# 9_-_STM32F407_Controller.net
KiCad netlist of a schematic drawn in Altium Designer
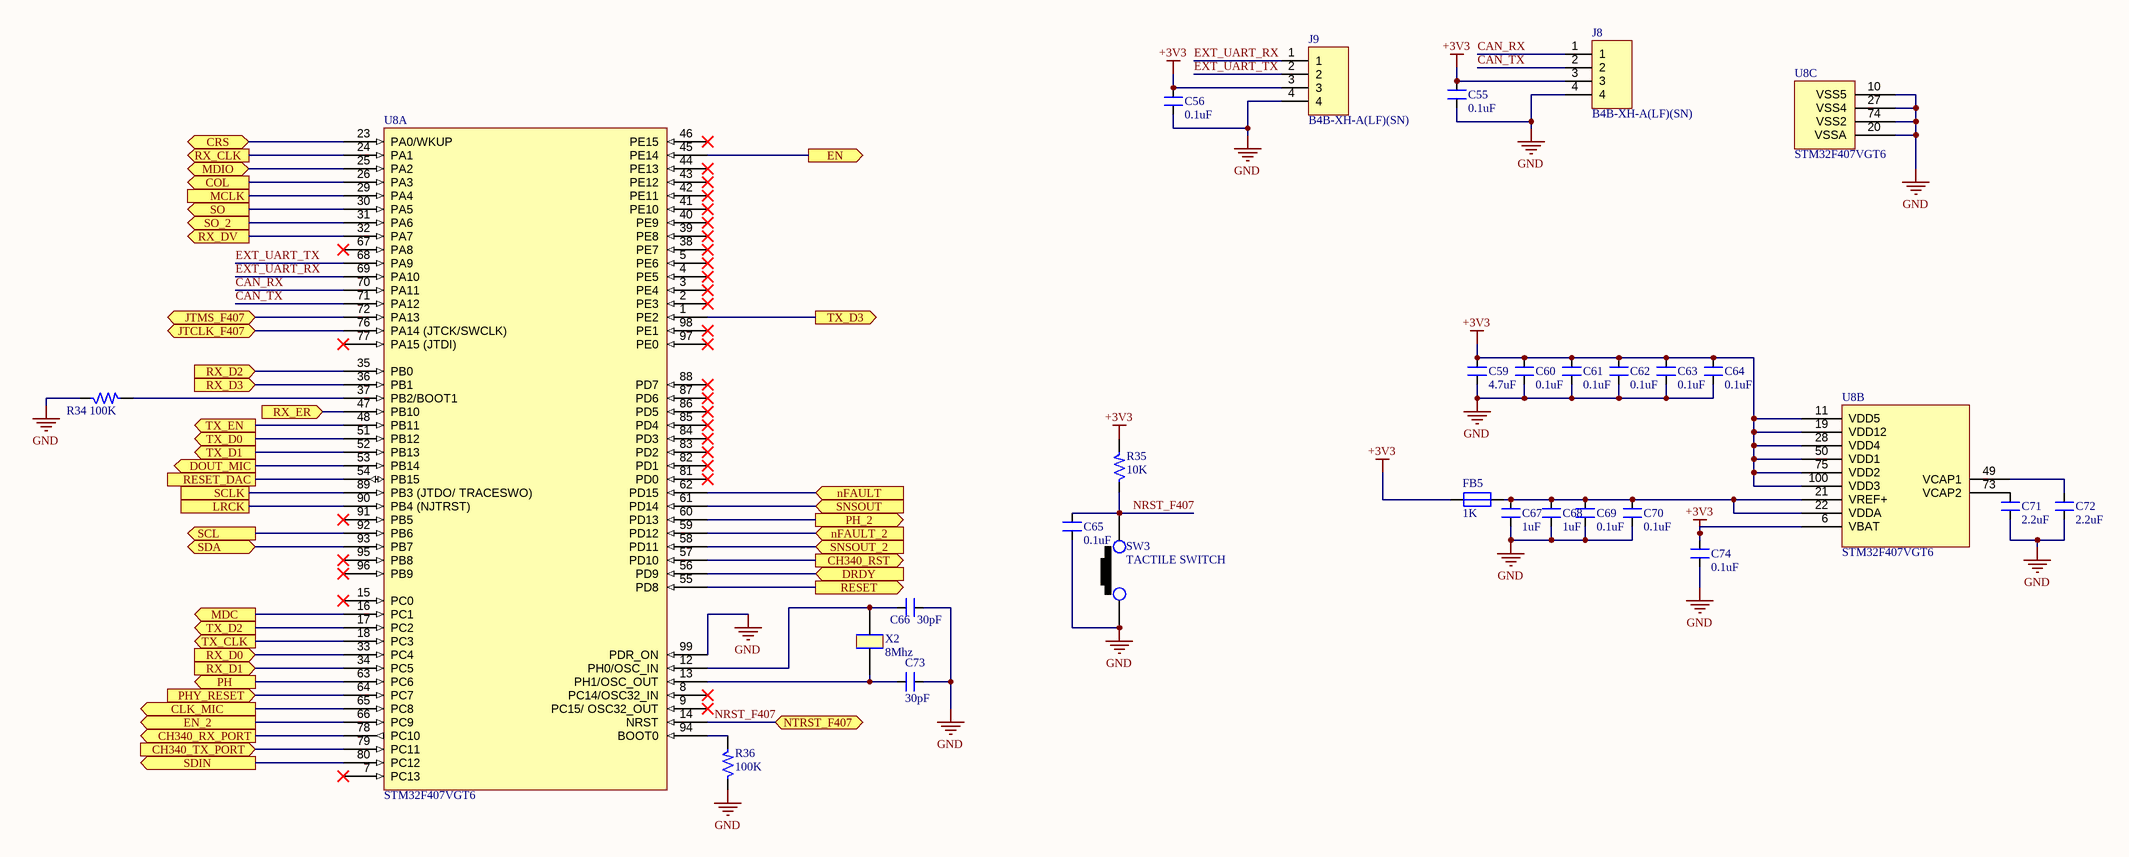
[diagram p0: [9] - STM32F407 Controller.SchDoc]

(export (version "E")
  (design (tool "Eeschema 10.0.6"))
  (components
    (comp (ref "C55")
      (value "0.1uF")
      (footprint "CAP_0805")
      (description "0.1µF ±10% 50V Ceramic Capacitor X7R 0805 (2012 Metric)")
      (fields
        (field (name "MANUFACTURER") "Samsung")
        (field (name "MANUFACTURER PART NUMBER") "CL21B104KBCNNNC")
      )
      (libsource (lib "ESTEEMPCBLIB") (part "CAP_0.1uF-50V-10%-0805"))
    )
    (comp (ref "C56")
      (value "0.1uF")
      (footprint "CAP_0805")
      (description "0.1µF ±10% 50V Ceramic Capacitor X7R 0805 (2012 Metric)")
      (fields
        (field (name "MANUFACTURER") "Samsung")
        (field (name "MANUFACTURER PART NUMBER") "CL21B104KBCNNNC")
      )
      (libsource (lib "ESTEEMPCBLIB") (part "CAP_0.1uF-50V-10%-0805"))
    )
    (comp (ref "C59")
      (value "4.7uF")
      (footprint "CAP_0805")
      (description "0.1µF ±10% 50V Ceramic Capacitor X7R 0805 (2012 Metric)")
      (fields
        (field (name "MANUFACTURER") "Samsung")
        (field (name "MANUFACTURER PART NUMBER") "CL21B104KBCNNNC")
      )
      (libsource (lib "ESTEEMPCBLIB") (part "CAP_0.1uF-50V-10%-0805"))
    )
    (comp (ref "C60")
      (value "0.1uF")
      (footprint "CAP_0805")
      (description "0.1µF ±10% 50V Ceramic Capacitor X7R 0805 (2012 Metric)")
      (fields
        (field (name "MANUFACTURER") "Samsung")
        (field (name "MANUFACTURER PART NUMBER") "CL21B104KBCNNNC")
      )
      (libsource (lib "ESTEEMPCBLIB") (part "CAP_0.1uF-50V-10%-0805"))
    )
    (comp (ref "C61")
      (value "0.1uF")
      (footprint "CAP_0805")
      (description "0.1µF ±10% 50V Ceramic Capacitor X7R 0805 (2012 Metric)")
      (fields
        (field (name "MANUFACTURER") "Samsung")
        (field (name "MANUFACTURER PART NUMBER") "CL21B104KBCNNNC")
      )
      (libsource (lib "ESTEEMPCBLIB") (part "CAP_0.1uF-50V-10%-0805"))
    )
    (comp (ref "C62")
      (value "0.1uF")
      (footprint "CAP_0805")
      (description "0.1µF ±10% 50V Ceramic Capacitor X7R 0805 (2012 Metric)")
      (fields
        (field (name "MANUFACTURER") "Samsung")
        (field (name "MANUFACTURER PART NUMBER") "CL21B104KBCNNNC")
      )
      (libsource (lib "ESTEEMPCBLIB") (part "CAP_0.1uF-50V-10%-0805"))
    )
    (comp (ref "C63")
      (value "0.1uF")
      (footprint "CAP_0805")
      (description "0.1µF ±10% 50V Ceramic Capacitor X7R 0805 (2012 Metric)")
      (fields
        (field (name "MANUFACTURER") "Samsung")
        (field (name "MANUFACTURER PART NUMBER") "CL21B104KBCNNNC")
      )
      (libsource (lib "ESTEEMPCBLIB") (part "CAP_0.1uF-50V-10%-0805"))
    )
    (comp (ref "C64")
      (value "0.1uF")
      (footprint "CAP_0805")
      (description "0.1µF ±10% 50V Ceramic Capacitor X7R 0805 (2012 Metric)")
      (fields
        (field (name "MANUFACTURER") "Samsung")
        (field (name "MANUFACTURER PART NUMBER") "CL21B104KBCNNNC")
      )
      (libsource (lib "ESTEEMPCBLIB") (part "CAP_0.1uF-50V-10%-0805"))
    )
    (comp (ref "C65")
      (value "0.1uF")
      (footprint "CAP_0805")
      (description "0.1µF ±10% 50V Ceramic Capacitor X7R 0805 (2012 Metric)")
      (fields
        (field (name "MANUFACTURER") "Samsung")
        (field (name "MANUFACTURER PART NUMBER") "CL21B104KBCNNNC")
      )
      (libsource (lib "ESTEEMPCBLIB") (part "CAP_0.1uF-50V-10%-0805"))
    )
    (comp (ref "C66")
      (value "30pF")
      (footprint "CAP_0805")
      (description "±10% 50V Ceramic Capacitor C0G, NP0 0805 (2012 Metric)")
      (fields
        (field (name "MANUFACTURER PART NUMBER") "C0805C300K5GAC7800")
        (field (name "MANUFACTURER") "KEMET")
      )
      (libsource (lib "ESTEEMPCBLIB") (part "CAP_30pF-50V-10%-0805"))
    )
    (comp (ref "C67")
      (value "1uF")
      (footprint "CAP_0805")
      (description "1µF ±5% 50V Ceramic Capacitor X7R 0805 (2012 Metric)")
      (fields
        (field (name "MANUFACTURER") "Samsung")
        (field (name "MANUFACTURER PART NUMBER") "CC0805JKX7R9BB105")
      )
      (libsource (lib "ESTEEMPCBLIB") (part "CAP_1uF-50V-5%-0805"))
    )
    (comp (ref "C68")
      (value "1uF")
      (footprint "CAP_0805")
      (description "1µF ±5% 50V Ceramic Capacitor X7R 0805 (2012 Metric)")
      (fields
        (field (name "MANUFACTURER") "Samsung")
        (field (name "MANUFACTURER PART NUMBER") "CC0805JKX7R9BB105")
      )
      (libsource (lib "ESTEEMPCBLIB") (part "CAP_1uF-50V-5%-0805"))
    )
    (comp (ref "C69")
      (value "0.1uF")
      (footprint "CAP_0805")
      (description "0.1µF ±10% 50V Ceramic Capacitor X7R 0805 (2012 Metric)")
      (fields
        (field (name "MANUFACTURER") "Samsung")
        (field (name "MANUFACTURER PART NUMBER") "CL21B104KBCNNNC")
      )
      (libsource (lib "ESTEEMPCBLIB") (part "CAP_0.1uF-50V-10%-0805"))
    )
    (comp (ref "C70")
      (value "0.1uF")
      (footprint "CAP_0805")
      (description "0.1µF ±10% 50V Ceramic Capacitor X7R 0805 (2012 Metric)")
      (fields
        (field (name "MANUFACTURER") "Samsung")
        (field (name "MANUFACTURER PART NUMBER") "CL21B104KBCNNNC")
      )
      (libsource (lib "ESTEEMPCBLIB") (part "CAP_0.1uF-50V-10%-0805"))
    )
    (comp (ref "C71")
      (value "2.2uF")
      (footprint "CAP_0805")
      (description "2.2µF ±10% 25V Ceramic Capacitor X7R 0805 (2012 Metric)")
      (fields
        (field (name "MANUFACTURER") "KEMET")
        (field (name "MANUFACTURER PART NUMBER") "CL21B225KAFNFNE")
      )
      (libsource (lib "ESTEEMPCBLIB") (part "CAP_2.2uF-25V-10%-0805"))
    )
    (comp (ref "C72")
      (value "2.2uF")
      (footprint "CAP_0805")
      (description "2.2µF ±10% 25V Ceramic Capacitor X7R 0805 (2012 Metric)")
      (fields
        (field (name "MANUFACTURER") "KEMET")
        (field (name "MANUFACTURER PART NUMBER") "CL21B225KAFNFNE")
      )
      (libsource (lib "ESTEEMPCBLIB") (part "CAP_2.2uF-25V-10%-0805"))
    )
    (comp (ref "C73")
      (value "30pF")
      (footprint "CAP_0805")
      (description "±10% 50V Ceramic Capacitor C0G, NP0 0805 (2012 Metric)")
      (fields
        (field (name "MANUFACTURER PART NUMBER") "C0805C300K5GAC7800")
        (field (name "MANUFACTURER") "KEMET")
      )
      (libsource (lib "ESTEEMPCBLIB") (part "CAP_30pF-50V-10%-0805"))
    )
    (comp (ref "C74")
      (value "0.1uF")
      (footprint "CAP_0805")
      (description "0.1µF ±10% 50V Ceramic Capacitor X7R 0805 (2012 Metric)")
      (fields
        (field (name "MANUFACTURER") "Samsung")
        (field (name "MANUFACTURER PART NUMBER") "CL21B104KBCNNNC")
      )
      (libsource (lib "ESTEEMPCBLIB") (part "CAP_0.1uF-50V-10%-0805"))
    )
    (comp (ref "FB5")
      (value "1K")
      (footprint "IND_0805")
      (description "1 kOhms @ 100MHz 1 Power Line Ferrite Bead 0805 (2012 Metric) 1.6A")
      (fields
        (field (name "MANUFACTURER") "Laird")
        (field (name "MANUFACTURER PART NUMBER") "BLM21SP102SH1D")
      )
      (libsource (lib "ESTEEMPCBLIB") (part "FB_1K-100MHZ-1.6A-0805"))
    )
    (comp (ref "J8")
      (value "B4B-XH-A(LF)(SN)")
      (footprint "CON4_100_B4B-XH-A_TH_ST")
      (description "4 Pins, 1 Row 2.54mm Pitch, straight Connector, male")
      (fields (field (name "MANUFACTURER") "Wurth Electronics") (field (name "MATING PART NUMBER") "XHP-4"))
      (libsource (lib "ESTEEMPCBLIB") (part "CON-PLG_4X1-100-ST-TH"))
    )
    (comp (ref "J9")
      (value "B4B-XH-A(LF)(SN)")
      (footprint "CON4_100_B4B-XH-A_TH_ST")
      (description "4 Pins, 1 Row 2.54mm Pitch, straight Connector, male")
      (fields (field (name "MANUFACTURER") "Wurth Electronics") (field (name "MATING PART NUMBER") "XHP-4"))
      (libsource (lib "ESTEEMPCBLIB") (part "CON-PLG_4X1-100-ST-TH"))
    )
    (comp (ref "R34")
      (value "100K")
      (footprint "RES_0603")
      (description "100 kOhms ±1% 0.1W, 1/10W Chip Resistor 0603 (1608 Metric) Automotive AEC-Q200 Thick Film")
      (fields
        (field (name "MANUFACTURER") "Stackpole Electronics")
        (field (name "MANUFACTURER PART NUMBER") "RMCF0603FT100K")
      )
      (libsource (lib "ESTEEMPCBLIB") (part "RES_100K-0.1W-1%-0603"))
    )
    (comp (ref "R35")
      (value "10K")
      (footprint "RES_0603")
      (description "10 kOhms ±1% 0.1W, 1/10W Chip Resistor 0603 (1608 Metric) Automotive AEC-Q200 Thick Film")
      (fields (field (name "MANUFACTURER") "Walsin") (field (name "MANUFACTURER PART NUMBER") "WR06X1002FTL"))
      (libsource (lib "ESTEEMPCBLIB") (part "RES_10K-0.1W-1%-0603"))
    )
    (comp (ref "R36")
      (value "100K")
      (footprint "RES_0603")
      (description "100 kOhms ±1% 0.1W, 1/10W Chip Resistor 0603 (1608 Metric) Automotive AEC-Q200 Thick Film")
      (fields
        (field (name "MANUFACTURER") "Stackpole Electronics")
        (field (name "MANUFACTURER PART NUMBER") "RMCF0603FT100K")
      )
      (libsource (lib "ESTEEMPCBLIB") (part "RES_100K-0.1W-1%-0603"))
    )
    (comp (ref "SW3")
      (value "TACTILE SWITCH")
      (footprint "SW_342_SMD")
      (description "Tactile Switch SPST-NO Top Actuated Surface Mount")
      (fields
        (field (name "MANUFACTURER") "ITT C&K")
        (field (name "MANUFACTURER PART NUMBER") "RS-282G05A3-SMRT")
      )
      (libsource (lib "ESTEEMPCBLIB") (part "SW1_RS-282G05A3-SMRT-SMD"))
    )
    (comp (ref "U8")
      (value "STM32F407VGT6")
      (footprint "QFN100_19.6_669_58X10_SMD")
      (description "ARM® Cortex®-M4 STM32F4 Microcontroller IC 32-Bit 168MHz 1MB (1M x 8) FLASH 100-LQFP (14x14)")
      (fields (field (name "MANUFACTURER") "STMicroelectronics"))
      (libsource (lib "ESTEEMPCBLIB") (part "IC_STM32F407VGT6"))
    )
    (comp (ref "X2")
      (value "8Mhz")
      (footprint "XTAL_314_240X47_SMD")
      (description "8MHz ±30ppm Crystal 32pF 60 Ohms HC-49/US")
      (fields
        (field (name "MANUFACTURER") "Fox Electronics")
        (field (name "MANUFACTURER PART NUMBER") "ECS-80-32-5PX-TR")
      )
      (libsource (lib "ESTEEMPCBLIB") (part "XTAL_8MHZ-ECS-80-32-5PX-SMD"))
    )
  )
  (nets
    (net (code "1") (name "+3V3") (class "Default")
      (node (ref "C55") (pin "2") (pinfunction "2_2") (pintype "passive"))
      (node (ref "C56") (pin "2") (pinfunction "2_2") (pintype "passive"))
      (node (ref "C59") (pin "2") (pinfunction "2_2") (pintype "passive"))
      (node (ref "C60") (pin "2") (pinfunction "2_2") (pintype "passive"))
      (node (ref "C61") (pin "2") (pinfunction "2_2") (pintype "passive"))
      (node (ref "C62") (pin "2") (pinfunction "2_2") (pintype "passive"))
      (node (ref "C63") (pin "2") (pinfunction "2_2") (pintype "passive"))
      (node (ref "C64") (pin "2") (pinfunction "2_2") (pintype "passive"))
      (node (ref "C74") (pin "2") (pinfunction "2_2") (pintype "passive"))
      (node (ref "FB5") (pin "1") (pinfunction "1_1") (pintype "passive"))
      (node (ref "J8") (pin "3") (pinfunction "3_3") (pintype "passive"))
      (node (ref "J9") (pin "3") (pinfunction "3_3") (pintype "passive"))
      (node (ref "R35") (pin "2") (pinfunction "2_2") (pintype "passive"))
      (node (ref "U8") (pin "100") (pinfunction "VDD3_100") (pintype "passive"))
      (node (ref "U8") (pin "11") (pinfunction "VDD5_11") (pintype "passive"))
      (node (ref "U8") (pin "19") (pinfunction "VDD12_19") (pintype "passive"))
      (node (ref "U8") (pin "28") (pinfunction "VDD4_28") (pintype "passive"))
      (node (ref "U8") (pin "50") (pinfunction "VDD1_50") (pintype "passive"))
      (node (ref "U8") (pin "6") (pinfunction "VBAT_6") (pintype "passive"))
      (node (ref "U8") (pin "75") (pinfunction "VDD2_75") (pintype "passive"))
    )
    (net (code "2") (name "/CAN_RX") (class "Default")
      (node (ref "J8") (pin "1") (pinfunction "1_1") (pintype "passive"))
      (node (ref "U8") (pin "70") (pinfunction "PA11_70") (pintype "input"))
    )
    (net (code "3") (name "/CAN_TX") (class "Default")
      (node (ref "J8") (pin "2") (pinfunction "2_2") (pintype "passive"))
      (node (ref "U8") (pin "71") (pinfunction "PA12_71") (pintype "input"))
    )
    (net (code "4") (name "/CH340_RST") (class "Default")
      (node (ref "U8") (pin "57") (pinfunction "PD10_57") (pintype "input"))
    )
    (net (code "5") (name "/CH340_RX_PORT") (class "Default")
      (node (ref "U8") (pin "78") (pinfunction "PC10_78") (pintype "output"))
    )
    (net (code "6") (name "/CH340_TX_PORT") (class "Default")
      (node (ref "U8") (pin "79") (pinfunction "PC11_79") (pintype "input"))
    )
    (net (code "7") (name "/CLK_MIC") (class "Default")
      (node (ref "U8") (pin "65") (pinfunction "PC8_65") (pintype "input"))
    )
    (net (code "8") (name "/COL") (class "Default")
      (node (ref "U8") (pin "26") (pinfunction "PA3_26") (pintype "input"))
    )
    (net (code "9") (name "/CRS") (class "Default")
      (node (ref "U8") (pin "23") (pinfunction "PA0/WKUP_23") (pintype "input"))
    )
    (net (code "10") (name "/DOUT_MIC") (class "Default")
      (node (ref "U8") (pin "53") (pinfunction "PB14_53") (pintype "input"))
    )
    (net (code "11") (name "/DRDY") (class "Default")
      (node (ref "U8") (pin "56") (pinfunction "PD9_56") (pintype "input"))
    )
    (net (code "12") (name "/EN") (class "Default")
      (node (ref "U8") (pin "45") (pinfunction "PE14_45") (pintype "input"))
    )
    (net (code "13") (name "/EN_2") (class "Default")
      (node (ref "U8") (pin "66") (pinfunction "PC9_66") (pintype "input"))
    )
    (net (code "14") (name "/EXT_UART_RX") (class "Default")
      (node (ref "J9") (pin "1") (pinfunction "1_1") (pintype "passive"))
      (node (ref "U8") (pin "69") (pinfunction "PA10_69") (pintype "input"))
    )
    (net (code "15") (name "/EXT_UART_TX") (class "Default")
      (node (ref "J9") (pin "2") (pinfunction "2_2") (pintype "passive"))
      (node (ref "U8") (pin "68") (pinfunction "PA9_68") (pintype "input"))
    )
    (net (code "16") (name "/JTCLK_F407") (class "Default")
      (node (ref "U8") (pin "76") (pinfunction "PA14_(JTCK/SWCLK)_76") (pintype "input"))
    )
    (net (code "17") (name "/JTMS_F407") (class "Default")
      (node (ref "U8") (pin "72") (pinfunction "PA13_72") (pintype "input"))
    )
    (net (code "18") (name "/LRCK") (class "Default")
      (node (ref "U8") (pin "90") (pinfunction "PB4_(NJTRST)_90") (pintype "input"))
    )
    (net (code "19") (name "/MCLK") (class "Default")
      (node (ref "U8") (pin "29") (pinfunction "PA4_29") (pintype "input"))
    )
    (net (code "20") (name "/MDC") (class "Default")
      (node (ref "U8") (pin "16") (pinfunction "PC1_16") (pintype "input"))
    )
    (net (code "21") (name "/MDIO") (class "Default")
      (node (ref "U8") (pin "25") (pinfunction "PA2_25") (pintype "input"))
    )
    (net (code "22") (name "/NRST_F407") (class "Default")
      (node (ref "C65") (pin "2") (pinfunction "2_2") (pintype "passive"))
      (node (ref "R35") (pin "1") (pinfunction "1_1") (pintype "passive"))
      (node (ref "SW3") (pin "2") (pinfunction "2_2") (pintype "passive"))
      (node (ref "U8") (pin "14") (pinfunction "NRST_14") (pintype "input"))
    )
    (net (code "23") (name "/PH") (class "Default")
      (node (ref "U8") (pin "63") (pinfunction "PC6_63") (pintype "input"))
    )
    (net (code "24") (name "/PHY_RESET") (class "Default")
      (node (ref "U8") (pin "64") (pinfunction "PC7_64") (pintype "input"))
    )
    (net (code "25") (name "/PH_2") (class "Default")
      (node (ref "U8") (pin "60") (pinfunction "PD13_60") (pintype "input"))
    )
    (net (code "26") (name "/RESET") (class "Default")
      (node (ref "U8") (pin "55") (pinfunction "PD8_55") (pintype "input"))
    )
    (net (code "27") (name "/RESET_DAC") (class "Default")
      (node (ref "U8") (pin "54") (pinfunction "PB15_54") (pintype "bidirectional"))
    )
    (net (code "28") (name "/RX_CLK") (class "Default")
      (node (ref "U8") (pin "24") (pinfunction "PA1_24") (pintype "input"))
    )
    (net (code "29") (name "/RX_D0") (class "Default")
      (node (ref "U8") (pin "33") (pinfunction "PC4_33") (pintype "input"))
    )
    (net (code "30") (name "/RX_D1") (class "Default")
      (node (ref "U8") (pin "34") (pinfunction "PC5_34") (pintype "input"))
    )
    (net (code "31") (name "/RX_D2") (class "Default")
      (node (ref "U8") (pin "35") (pinfunction "PB0_35") (pintype "input"))
    )
    (net (code "32") (name "/RX_D3") (class "Default")
      (node (ref "U8") (pin "36") (pinfunction "PB1_36") (pintype "input"))
    )
    (net (code "33") (name "/RX_DV") (class "Default")
      (node (ref "U8") (pin "32") (pinfunction "PA7_32") (pintype "input"))
    )
    (net (code "34") (name "/RX_ER") (class "Default")
      (node (ref "U8") (pin "47") (pinfunction "PB10_47") (pintype "input"))
    )
    (net (code "35") (name "/SCL") (class "Default")
      (node (ref "U8") (pin "92") (pinfunction "PB6_92") (pintype "input"))
    )
    (net (code "36") (name "/SCLK") (class "Default")
      (node (ref "U8") (pin "89") (pinfunction "PB3_(JTDO/_TRACESWO)_89") (pintype "input"))
    )
    (net (code "37") (name "/SDA") (class "Default")
      (node (ref "U8") (pin "93") (pinfunction "PB7_93") (pintype "input"))
    )
    (net (code "38") (name "/SDIN") (class "Default")
      (node (ref "U8") (pin "80") (pinfunction "PC12_80") (pintype "input"))
    )
    (net (code "39") (name "/SNSOUT") (class "Default")
      (node (ref "U8") (pin "61") (pinfunction "PD14_61") (pintype "input"))
    )
    (net (code "40") (name "/SNSOUT_2") (class "Default")
      (node (ref "U8") (pin "58") (pinfunction "PD11_58") (pintype "input"))
    )
    (net (code "41") (name "/SO") (class "Default")
      (node (ref "U8") (pin "30") (pinfunction "PA5_30") (pintype "input"))
    )
    (net (code "42") (name "/SO_2") (class "Default")
      (node (ref "U8") (pin "31") (pinfunction "PA6_31") (pintype "input"))
    )
    (net (code "43") (name "/TX_CLK") (class "Default")
      (node (ref "U8") (pin "18") (pinfunction "PC3_18") (pintype "input"))
    )
    (net (code "44") (name "/TX_D0") (class "Default")
      (node (ref "U8") (pin "51") (pinfunction "PB12_51") (pintype "input"))
    )
    (net (code "45") (name "/TX_D1") (class "Default")
      (node (ref "U8") (pin "52") (pinfunction "PB13_52") (pintype "input"))
    )
    (net (code "46") (name "/TX_D2") (class "Default")
      (node (ref "U8") (pin "17") (pinfunction "PC2_17") (pintype "input"))
    )
    (net (code "47") (name "/TX_D3") (class "Default")
      (node (ref "U8") (pin "1") (pinfunction "PE2_1") (pintype "input"))
    )
    (net (code "48") (name "/TX_EN") (class "Default")
      (node (ref "U8") (pin "48") (pinfunction "PB11_48") (pintype "input"))
    )
    (net (code "49") (name "/nFAULT") (class "Default")
      (node (ref "U8") (pin "62") (pinfunction "PD15_62") (pintype "input"))
    )
    (net (code "50") (name "/nFAULT_2") (class "Default")
      (node (ref "U8") (pin "59") (pinfunction "PD12_59") (pintype "input"))
    )
    (net (code "51") (name "GND") (class "Default")
      (node (ref "C55") (pin "1") (pinfunction "1_1") (pintype "passive"))
      (node (ref "C56") (pin "1") (pinfunction "1_1") (pintype "passive"))
      (node (ref "C59") (pin "1") (pinfunction "1_1") (pintype "passive"))
      (node (ref "C60") (pin "1") (pinfunction "1_1") (pintype "passive"))
      (node (ref "C61") (pin "1") (pinfunction "1_1") (pintype "passive"))
      (node (ref "C62") (pin "1") (pinfunction "1_1") (pintype "passive"))
      (node (ref "C63") (pin "1") (pinfunction "1_1") (pintype "passive"))
      (node (ref "C64") (pin "1") (pinfunction "1_1") (pintype "passive"))
      (node (ref "C65") (pin "1") (pinfunction "1_1") (pintype "passive"))
      (node (ref "C66") (pin "1") (pinfunction "1_1") (pintype "passive"))
      (node (ref "C67") (pin "1") (pinfunction "1_1") (pintype "passive"))
      (node (ref "C68") (pin "1") (pinfunction "1_1") (pintype "passive"))
      (node (ref "C69") (pin "1") (pinfunction "1_1") (pintype "passive"))
      (node (ref "C70") (pin "1") (pinfunction "1_1") (pintype "passive"))
      (node (ref "C71") (pin "1") (pinfunction "1_1") (pintype "passive"))
      (node (ref "C72") (pin "1") (pinfunction "1_1") (pintype "passive"))
      (node (ref "C73") (pin "1") (pinfunction "1_1") (pintype "passive"))
      (node (ref "C74") (pin "1") (pinfunction "1_1") (pintype "passive"))
      (node (ref "J8") (pin "4") (pinfunction "4_4") (pintype "passive"))
      (node (ref "J9") (pin "4") (pinfunction "4_4") (pintype "passive"))
      (node (ref "R34") (pin "1") (pinfunction "1_1") (pintype "passive"))
      (node (ref "R36") (pin "1") (pinfunction "1_1") (pintype "passive"))
      (node (ref "SW3") (pin "1") (pinfunction "1_1") (pintype "passive"))
      (node (ref "U8") (pin "10") (pinfunction "VSS5_10") (pintype "passive"))
      (node (ref "U8") (pin "20") (pinfunction "VSSA_20") (pintype "passive"))
      (node (ref "U8") (pin "27") (pinfunction "VSS4_27") (pintype "passive"))
      (node (ref "U8") (pin "74") (pinfunction "VSS2_74") (pintype "passive"))
      (node (ref "U8") (pin "99") (pinfunction "PDR_ON_99") (pintype "input"))
    )
    (net (code "52") (name "Net-(U8A-BOOT0)") (class "Default")
      (node (ref "R36") (pin "2") (pinfunction "2_2") (pintype "passive"))
      (node (ref "U8") (pin "94") (pinfunction "BOOT0_94") (pintype "input"))
    )
    (net (code "53") (name "Net-(U8A-PB2{slash}BOOT1)") (class "Default")
      (node (ref "R34") (pin "2") (pinfunction "2_2") (pintype "passive"))
      (node (ref "U8") (pin "37") (pinfunction "PB2/BOOT1_37") (pintype "input"))
    )
    (net (code "54") (name "Net-(U8A-PH0{slash}OSC_IN)") (class "Default")
      (node (ref "C66") (pin "2") (pinfunction "2_2") (pintype "passive"))
      (node (ref "U8") (pin "12") (pinfunction "PH0/OSC_IN_12") (pintype "input"))
      (node (ref "X2") (pin "2") (pinfunction "2_2") (pintype "passive"))
    )
    (net (code "55") (name "Net-(U8A-PH1{slash}OSC_OUT)") (class "Default")
      (node (ref "C73") (pin "2") (pinfunction "2_2") (pintype "passive"))
      (node (ref "U8") (pin "13") (pinfunction "PH1/OSC_OUT_13") (pintype "input"))
      (node (ref "X2") (pin "1") (pinfunction "1_1") (pintype "passive"))
    )
    (net (code "56") (name "Net-(U8B-VCAP1)") (class "Default")
      (node (ref "C72") (pin "2") (pinfunction "2_2") (pintype "passive"))
      (node (ref "U8") (pin "49") (pinfunction "VCAP1_49") (pintype "passive"))
    )
    (net (code "57") (name "Net-(U8B-VCAP2)") (class "Default")
      (node (ref "C71") (pin "2") (pinfunction "2_2") (pintype "passive"))
      (node (ref "U8") (pin "73") (pinfunction "VCAP2_73") (pintype "passive"))
    )
    (net (code "58") (name "Net-(U8B-VDDA)") (class "Default")
      (node (ref "C67") (pin "2") (pinfunction "2_2") (pintype "passive"))
      (node (ref "C68") (pin "2") (pinfunction "2_2") (pintype "passive"))
      (node (ref "C69") (pin "2") (pinfunction "2_2") (pintype "passive"))
      (node (ref "C70") (pin "2") (pinfunction "2_2") (pintype "passive"))
      (node (ref "FB5") (pin "2") (pinfunction "2_2") (pintype "passive"))
      (node (ref "U8") (pin "21") (pinfunction "VREF+_21") (pintype "passive"))
      (node (ref "U8") (pin "22") (pinfunction "VDDA_22") (pintype "passive"))
    )
    (net (code "59") (name "unconnected-(U8A-PA8-Pad67)") (class "Default")
      (node (ref "U8") (pin "67") (pinfunction "PA8_67") (pintype "input+no_connect"))
    )
    (net (code "60") (name "unconnected-(U8A-PA15_(JTDI)-Pad77)") (class "Default")
      (node (ref "U8") (pin "77") (pinfunction "PA15_(JTDI)_77") (pintype "input+no_connect"))
    )
    (net (code "61") (name "unconnected-(U8A-PB5-Pad91)") (class "Default")
      (node (ref "U8") (pin "91") (pinfunction "PB5_91") (pintype "input+no_connect"))
    )
    (net (code "62") (name "unconnected-(U8A-PB8-Pad95)") (class "Default")
      (node (ref "U8") (pin "95") (pinfunction "PB8_95") (pintype "input+no_connect"))
    )
    (net (code "63") (name "unconnected-(U8A-PB9-Pad96)") (class "Default")
      (node (ref "U8") (pin "96") (pinfunction "PB9_96") (pintype "input+no_connect"))
    )
    (net (code "64") (name "unconnected-(U8A-PC0-Pad15)") (class "Default")
      (node (ref "U8") (pin "15") (pinfunction "PC0_15") (pintype "input+no_connect"))
    )
    (net (code "65") (name "unconnected-(U8A-PC13-Pad7)") (class "Default")
      (node (ref "U8") (pin "7") (pinfunction "PC13_7") (pintype "input+no_connect"))
    )
    (net (code "66") (name "unconnected-(U8A-PC14{slash}OSC32_IN-Pad8)") (class "Default")
      (node (ref "U8") (pin "8") (pinfunction "PC14/OSC32_IN_8") (pintype "input+no_connect"))
    )
    (net (code "67") (name "unconnected-(U8A-PC15{slash}_OSC32_OUT-Pad9)") (class "Default")
      (node (ref "U8") (pin "9") (pinfunction "PC15/_OSC32_OUT_9") (pintype "input+no_connect"))
    )
    (net (code "68") (name "unconnected-(U8A-PD0-Pad81)") (class "Default")
      (node (ref "U8") (pin "81") (pinfunction "PD0_81") (pintype "input+no_connect"))
    )
    (net (code "69") (name "unconnected-(U8A-PD1-Pad82)") (class "Default")
      (node (ref "U8") (pin "82") (pinfunction "PD1_82") (pintype "input+no_connect"))
    )
    (net (code "70") (name "unconnected-(U8A-PD2-Pad83)") (class "Default")
      (node (ref "U8") (pin "83") (pinfunction "PD2_83") (pintype "input+no_connect"))
    )
    (net (code "71") (name "unconnected-(U8A-PD3-Pad84)") (class "Default")
      (node (ref "U8") (pin "84") (pinfunction "PD3_84") (pintype "input+no_connect"))
    )
    (net (code "72") (name "unconnected-(U8A-PD4-Pad85)") (class "Default")
      (node (ref "U8") (pin "85") (pinfunction "PD4_85") (pintype "input+no_connect"))
    )
    (net (code "73") (name "unconnected-(U8A-PD5-Pad86)") (class "Default")
      (node (ref "U8") (pin "86") (pinfunction "PD5_86") (pintype "input+no_connect"))
    )
    (net (code "74") (name "unconnected-(U8A-PD6-Pad87)") (class "Default")
      (node (ref "U8") (pin "87") (pinfunction "PD6_87") (pintype "input+no_connect"))
    )
    (net (code "75") (name "unconnected-(U8A-PD7-Pad88)") (class "Default")
      (node (ref "U8") (pin "88") (pinfunction "PD7_88") (pintype "input+no_connect"))
    )
    (net (code "76") (name "unconnected-(U8A-PE0-Pad97)") (class "Default")
      (node (ref "U8") (pin "97") (pinfunction "PE0_97") (pintype "input+no_connect"))
    )
    (net (code "77") (name "unconnected-(U8A-PE1-Pad98)") (class "Default")
      (node (ref "U8") (pin "98") (pinfunction "PE1_98") (pintype "input+no_connect"))
    )
    (net (code "78") (name "unconnected-(U8A-PE3-Pad2)") (class "Default")
      (node (ref "U8") (pin "2") (pinfunction "PE3_2") (pintype "input+no_connect"))
    )
    (net (code "79") (name "unconnected-(U8A-PE4-Pad3)") (class "Default")
      (node (ref "U8") (pin "3") (pinfunction "PE4_3") (pintype "input+no_connect"))
    )
    (net (code "80") (name "unconnected-(U8A-PE5-Pad4)") (class "Default")
      (node (ref "U8") (pin "4") (pinfunction "PE5_4") (pintype "input+no_connect"))
    )
    (net (code "81") (name "unconnected-(U8A-PE6-Pad5)") (class "Default")
      (node (ref "U8") (pin "5") (pinfunction "PE6_5") (pintype "input+no_connect"))
    )
    (net (code "82") (name "unconnected-(U8A-PE7-Pad38)") (class "Default")
      (node (ref "U8") (pin "38") (pinfunction "PE7_38") (pintype "input+no_connect"))
    )
    (net (code "83") (name "unconnected-(U8A-PE8-Pad39)") (class "Default")
      (node (ref "U8") (pin "39") (pinfunction "PE8_39") (pintype "input+no_connect"))
    )
    (net (code "84") (name "unconnected-(U8A-PE9-Pad40)") (class "Default")
      (node (ref "U8") (pin "40") (pinfunction "PE9_40") (pintype "input+no_connect"))
    )
    (net (code "85") (name "unconnected-(U8A-PE10-Pad41)") (class "Default")
      (node (ref "U8") (pin "41") (pinfunction "PE10_41") (pintype "input+no_connect"))
    )
    (net (code "86") (name "unconnected-(U8A-PE11-Pad42)") (class "Default")
      (node (ref "U8") (pin "42") (pinfunction "PE11_42") (pintype "input+no_connect"))
    )
    (net (code "87") (name "unconnected-(U8A-PE12-Pad43)") (class "Default")
      (node (ref "U8") (pin "43") (pinfunction "PE12_43") (pintype "input+no_connect"))
    )
    (net (code "88") (name "unconnected-(U8A-PE13-Pad44)") (class "Default")
      (node (ref "U8") (pin "44") (pinfunction "PE13_44") (pintype "input+no_connect"))
    )
    (net (code "89") (name "unconnected-(U8A-PE15-Pad46)") (class "Default")
      (node (ref "U8") (pin "46") (pinfunction "PE15_46") (pintype "input+no_connect"))
    )
  )
)
